# kitt_db01.net
KiCad netlist of a schematic drawn in EAGLE
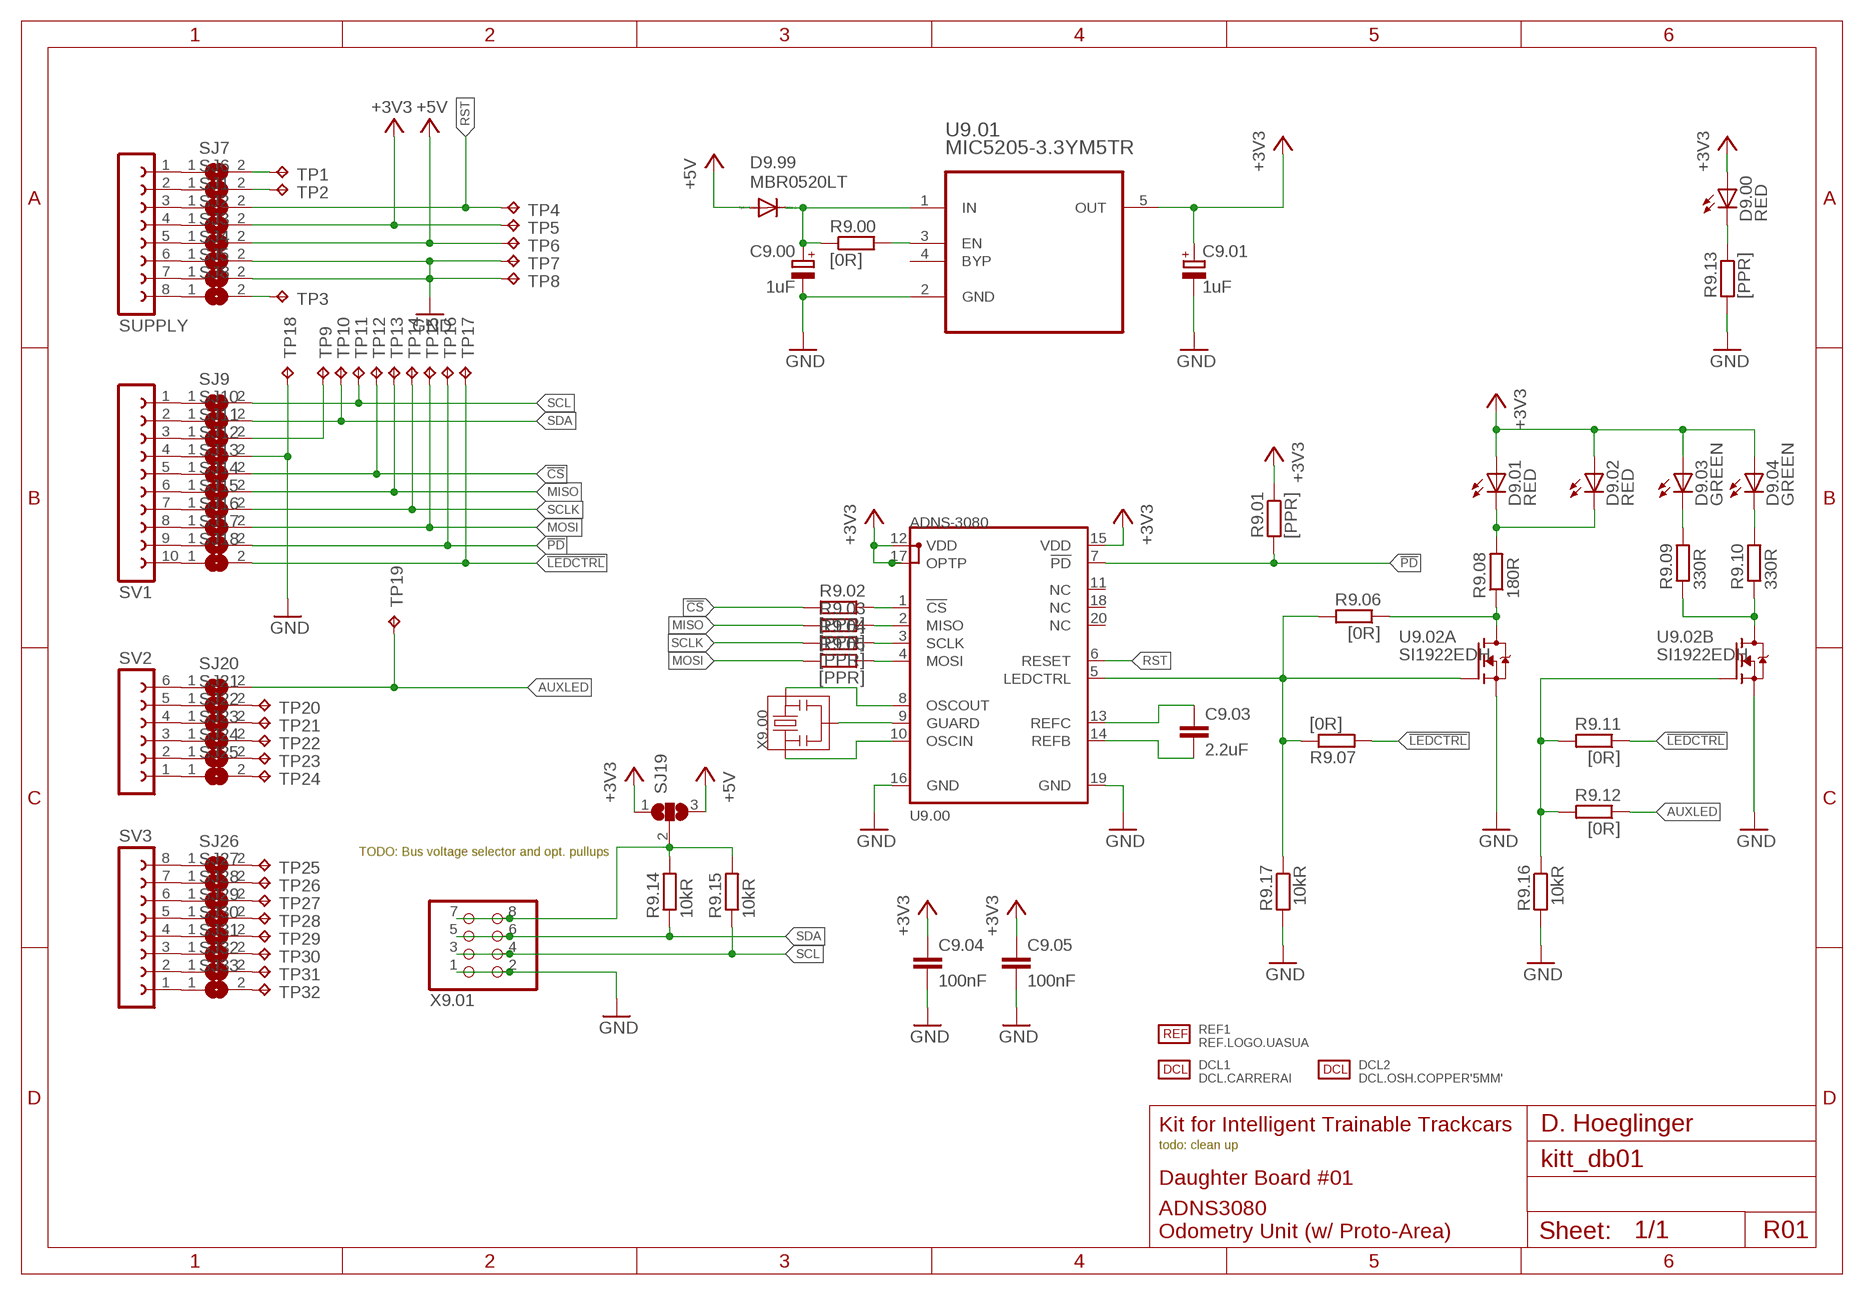
[diagram p0: schematic, sheet 1]

(export (version "E")
  (design (tool "Eeschema 10.0.6"))
  (components
    (comp (ref "C9.00")
      (value "1uF")
      (footprint "eagle-import:A_3216-18W")
      (libsource (lib "eagle-import") (part "CPOL-EUA/3216-18W"))
    )
    (comp (ref "C9.01")
      (value "1uF")
      (footprint "eagle-import:A_3216-18W")
      (libsource (lib "eagle-import") (part "CPOL-EUA/3216-18W"))
    )
    (comp (ref "C9.03")
      (value "2.2uF")
      (footprint "eagle-import:C1608")
      (libsource (lib "eagle-import") (part "C-EUC1608"))
    )
    (comp (ref "C9.04")
      (value "100nF")
      (footprint "eagle-import:C0805K")
      (libsource (lib "eagle-import") (part "C-EUC0805K"))
    )
    (comp (ref "C9.05")
      (value "100nF")
      (footprint "eagle-import:C0805K")
      (libsource (lib "eagle-import") (part "C-EUC0805K"))
    )
    (comp (ref "D9.00")
      (value "RED")
      (footprint "eagle-import:CHIP-LED0805")
      (libsource (lib "eagle-import") (part "LEDCHIP-LED0805"))
    )
    (comp (ref "D9.01")
      (value "RED")
      (footprint "eagle-import:LED5MM")
      (libsource (lib "eagle-import") (part "LED5MM"))
    )
    (comp (ref "D9.02")
      (value "RED")
      (footprint "eagle-import:CHIP-LED0805")
      (libsource (lib "eagle-import") (part "LEDCHIP-LED0805"))
    )
    (comp (ref "D9.03")
      (value "GREEN")
      (footprint "eagle-import:CHIP-LED0805")
      (libsource (lib "eagle-import") (part "LEDCHIP-LED0805"))
    )
    (comp (ref "D9.04")
      (value "GREEN")
      (footprint "eagle-import:CHIP-LED0805")
      (libsource (lib "eagle-import") (part "LEDCHIP-LED0805"))
    )
    (comp (ref "D9.99")
      (value "MBR0520LT")
      (footprint "eagle-import:SOD123")
      (libsource (lib "eagle-import") (part "MBR0520LT"))
    )
    (comp (ref "DCL1")
      (value "DCL.CARRERAI")
      (footprint "eagle-import:DCL.LOGO-CARRERAI.W30MM")
      (libsource (lib "eagle-import") (part "DCL.CARRERAI"))
    )
    (comp (ref "DCL2")
      (value "DCL.OSH.COPPER'5MM'")
      (footprint "eagle-import:DCL.LOGO-OSH.5MM")
      (libsource (lib "eagle-import") (part "DCL.OSH.COPPER'5MM'"))
    )
    (comp (ref "R9.00")
      (value "[0R]")
      (footprint "eagle-import:R0805")
      (libsource (lib "eagle-import") (part "R-EU_R0805"))
    )
    (comp (ref "R9.01")
      (value "[PPR]")
      (footprint "eagle-import:R0805")
      (libsource (lib "eagle-import") (part "R-EU_R0805"))
    )
    (comp (ref "R9.02")
      (value "[PPR]")
      (footprint "eagle-import:R0805")
      (libsource (lib "eagle-import") (part "R-EU_R0805"))
    )
    (comp (ref "R9.03")
      (value "[PPR]")
      (footprint "eagle-import:R0805")
      (libsource (lib "eagle-import") (part "R-EU_R0805"))
    )
    (comp (ref "R9.04")
      (value "[PPR]")
      (footprint "eagle-import:R0805")
      (libsource (lib "eagle-import") (part "R-EU_R0805"))
    )
    (comp (ref "R9.05")
      (value "[PPR]")
      (footprint "eagle-import:R0805")
      (libsource (lib "eagle-import") (part "R-EU_R0805"))
    )
    (comp (ref "R9.06")
      (value "[0R]")
      (footprint "eagle-import:R0805")
      (libsource (lib "eagle-import") (part "R-EU_R0805"))
    )
    (comp (ref "R9.07")
      (value "[0R]")
      (footprint "eagle-import:R0805")
      (libsource (lib "eagle-import") (part "R-EU_R0805"))
    )
    (comp (ref "R9.08")
      (value "180R")
      (footprint "eagle-import:R0805")
      (libsource (lib "eagle-import") (part "R-EU_R0805"))
    )
    (comp (ref "R9.09")
      (value "330R")
      (footprint "eagle-import:R0805")
      (libsource (lib "eagle-import") (part "R-EU_R0805"))
    )
    (comp (ref "R9.10")
      (value "330R")
      (footprint "eagle-import:R0805")
      (libsource (lib "eagle-import") (part "R-EU_R0805"))
    )
    (comp (ref "R9.11")
      (value "[0R]")
      (footprint "eagle-import:R0805")
      (libsource (lib "eagle-import") (part "R-EU_R0805"))
    )
    (comp (ref "R9.12")
      (value "[0R]")
      (footprint "eagle-import:R0805")
      (libsource (lib "eagle-import") (part "R-EU_R0805"))
    )
    (comp (ref "R9.13")
      (value "[PPR]")
      (footprint "eagle-import:R0805")
      (libsource (lib "eagle-import") (part "R-EU_R0805"))
    )
    (comp (ref "R9.14")
      (value "10kR")
      (footprint "eagle-import:R0805")
      (libsource (lib "eagle-import") (part "R-EU_R0805"))
    )
    (comp (ref "R9.15")
      (value "10kR")
      (footprint "eagle-import:R0805")
      (libsource (lib "eagle-import") (part "R-EU_R0805"))
    )
    (comp (ref "R9.16")
      (value "10kR")
      (footprint "eagle-import:R0805")
      (libsource (lib "eagle-import") (part "R-EU_R0805"))
    )
    (comp (ref "R9.17")
      (value "10kR")
      (footprint "eagle-import:R0805")
      (libsource (lib "eagle-import") (part "R-EU_R0805"))
    )
    (comp (ref "REF1")
      (value "REF.LOGO.UASUA")
      (footprint "eagle-import:REF_LOGO_UASUA")
      (libsource (lib "eagle-import") (part "REF.LOGO.UASUA"))
    )
    (comp (ref "SJ1") (value "SJ") (footprint "eagle-import:SJ") (libsource (lib "eagle-import") (part "SJ")))
    (comp (ref "SJ2") (value "SJ") (footprint "eagle-import:SJ") (libsource (lib "eagle-import") (part "SJ")))
    (comp (ref "SJ3") (value "SJ") (footprint "eagle-import:SJ") (libsource (lib "eagle-import") (part "SJ")))
    (comp (ref "SJ4") (value "SJ") (footprint "eagle-import:SJ") (libsource (lib "eagle-import") (part "SJ")))
    (comp (ref "SJ5") (value "SJ") (footprint "eagle-import:SJ") (libsource (lib "eagle-import") (part "SJ")))
    (comp (ref "SJ6") (value "SJ") (footprint "eagle-import:SJ") (libsource (lib "eagle-import") (part "SJ")))
    (comp (ref "SJ7") (value "SJ") (footprint "eagle-import:SJ") (libsource (lib "eagle-import") (part "SJ")))
    (comp (ref "SJ8") (value "SJ") (footprint "eagle-import:SJ") (libsource (lib "eagle-import") (part "SJ")))
    (comp (ref "SJ9") (value "SJ") (footprint "eagle-import:SJ") (libsource (lib "eagle-import") (part "SJ")))
    (comp (ref "SJ10")
      (value "SJ")
      (footprint "eagle-import:SJ")
      (libsource (lib "eagle-import") (part "SJ"))
    )
    (comp (ref "SJ11")
      (value "SJ")
      (footprint "eagle-import:SJ")
      (libsource (lib "eagle-import") (part "SJ"))
    )
    (comp (ref "SJ12")
      (value "SJ")
      (footprint "eagle-import:SJ")
      (libsource (lib "eagle-import") (part "SJ"))
    )
    (comp (ref "SJ13")
      (value "SJ")
      (footprint "eagle-import:SJ")
      (libsource (lib "eagle-import") (part "SJ"))
    )
    (comp (ref "SJ14")
      (value "SJ")
      (footprint "eagle-import:SJ")
      (libsource (lib "eagle-import") (part "SJ"))
    )
    (comp (ref "SJ15")
      (value "SJ")
      (footprint "eagle-import:SJ")
      (libsource (lib "eagle-import") (part "SJ"))
    )
    (comp (ref "SJ16")
      (value "SJ")
      (footprint "eagle-import:SJ")
      (libsource (lib "eagle-import") (part "SJ"))
    )
    (comp (ref "SJ17")
      (value "SJ")
      (footprint "eagle-import:SJ")
      (libsource (lib "eagle-import") (part "SJ"))
    )
    (comp (ref "SJ18")
      (value "SJ")
      (footprint "eagle-import:SJ")
      (libsource (lib "eagle-import") (part "SJ"))
    )
    (comp (ref "SJ19")
      (value "SJ2W")
      (footprint "eagle-import:SJ_2")
      (libsource (lib "eagle-import") (part "SJ2W"))
    )
    (comp (ref "SJ20")
      (value "SJ")
      (footprint "eagle-import:SJ")
      (libsource (lib "eagle-import") (part "SJ"))
    )
    (comp (ref "SJ21")
      (value "SJ")
      (footprint "eagle-import:SJ")
      (libsource (lib "eagle-import") (part "SJ"))
    )
    (comp (ref "SJ22")
      (value "SJ")
      (footprint "eagle-import:SJ")
      (libsource (lib "eagle-import") (part "SJ"))
    )
    (comp (ref "SJ23")
      (value "SJ")
      (footprint "eagle-import:SJ")
      (libsource (lib "eagle-import") (part "SJ"))
    )
    (comp (ref "SJ24")
      (value "SJ")
      (footprint "eagle-import:SJ")
      (libsource (lib "eagle-import") (part "SJ"))
    )
    (comp (ref "SJ25")
      (value "SJ")
      (footprint "eagle-import:SJ")
      (libsource (lib "eagle-import") (part "SJ"))
    )
    (comp (ref "SJ26")
      (value "SJ")
      (footprint "eagle-import:SJ")
      (libsource (lib "eagle-import") (part "SJ"))
    )
    (comp (ref "SJ27")
      (value "SJ")
      (footprint "eagle-import:SJ")
      (libsource (lib "eagle-import") (part "SJ"))
    )
    (comp (ref "SJ28")
      (value "SJ")
      (footprint "eagle-import:SJ")
      (libsource (lib "eagle-import") (part "SJ"))
    )
    (comp (ref "SJ29")
      (value "SJ")
      (footprint "eagle-import:SJ")
      (libsource (lib "eagle-import") (part "SJ"))
    )
    (comp (ref "SJ30")
      (value "SJ")
      (footprint "eagle-import:SJ")
      (libsource (lib "eagle-import") (part "SJ"))
    )
    (comp (ref "SJ31")
      (value "SJ")
      (footprint "eagle-import:SJ")
      (libsource (lib "eagle-import") (part "SJ"))
    )
    (comp (ref "SJ32")
      (value "SJ")
      (footprint "eagle-import:SJ")
      (libsource (lib "eagle-import") (part "SJ"))
    )
    (comp (ref "SJ33")
      (value "SJ")
      (footprint "eagle-import:SJ")
      (libsource (lib "eagle-import") (part "SJ"))
    )
    (comp (ref "SUPPLY")
      (value "FE08-1")
      (footprint "eagle-import:FE08")
      (libsource (lib "eagle-import") (part "FE08-1"))
    )
    (comp (ref "SV1")
      (value "FE10-1")
      (footprint "eagle-import:FE10")
      (libsource (lib "eagle-import") (part "FE10-1"))
    )
    (comp (ref "SV2")
      (value "FE06-1")
      (footprint "eagle-import:FE06")
      (libsource (lib "eagle-import") (part "FE06-1"))
    )
    (comp (ref "SV3")
      (value "FE08-1")
      (footprint "eagle-import:FE08")
      (libsource (lib "eagle-import") (part "FE08-1"))
    )
    (comp (ref "TP1")
      (value "TPPAD1-13")
      (footprint "eagle-import:P1-13")
      (libsource (lib "eagle-import") (part "TPPAD1-13"))
    )
    (comp (ref "TP2")
      (value "TPPAD1-13")
      (footprint "eagle-import:P1-13")
      (libsource (lib "eagle-import") (part "TPPAD1-13"))
    )
    (comp (ref "TP3")
      (value "TPPAD1-13")
      (footprint "eagle-import:P1-13")
      (libsource (lib "eagle-import") (part "TPPAD1-13"))
    )
    (comp (ref "TP4")
      (value "TPPAD1-13")
      (footprint "eagle-import:P1-13")
      (libsource (lib "eagle-import") (part "TPPAD1-13"))
    )
    (comp (ref "TP5")
      (value "TPPAD1-13")
      (footprint "eagle-import:P1-13")
      (libsource (lib "eagle-import") (part "TPPAD1-13"))
    )
    (comp (ref "TP6")
      (value "TPPAD1-13")
      (footprint "eagle-import:P1-13")
      (libsource (lib "eagle-import") (part "TPPAD1-13"))
    )
    (comp (ref "TP7")
      (value "TPPAD1-13")
      (footprint "eagle-import:P1-13")
      (libsource (lib "eagle-import") (part "TPPAD1-13"))
    )
    (comp (ref "TP8")
      (value "TPPAD1-13")
      (footprint "eagle-import:P1-13")
      (libsource (lib "eagle-import") (part "TPPAD1-13"))
    )
    (comp (ref "TP9")
      (value "TPPAD1-13")
      (footprint "eagle-import:P1-13")
      (libsource (lib "eagle-import") (part "TPPAD1-13"))
    )
    (comp (ref "TP10")
      (value "TPPAD1-13")
      (footprint "eagle-import:P1-13")
      (libsource (lib "eagle-import") (part "TPPAD1-13"))
    )
    (comp (ref "TP11")
      (value "TPPAD1-13")
      (footprint "eagle-import:P1-13")
      (libsource (lib "eagle-import") (part "TPPAD1-13"))
    )
    (comp (ref "TP12")
      (value "TPPAD1-13")
      (footprint "eagle-import:P1-13")
      (libsource (lib "eagle-import") (part "TPPAD1-13"))
    )
    (comp (ref "TP13")
      (value "TPPAD1-13")
      (footprint "eagle-import:P1-13")
      (libsource (lib "eagle-import") (part "TPPAD1-13"))
    )
    (comp (ref "TP14")
      (value "TPPAD1-13")
      (footprint "eagle-import:P1-13")
      (libsource (lib "eagle-import") (part "TPPAD1-13"))
    )
    (comp (ref "TP15")
      (value "TPPAD1-13")
      (footprint "eagle-import:P1-13")
      (libsource (lib "eagle-import") (part "TPPAD1-13"))
    )
    (comp (ref "TP16")
      (value "TPPAD1-13")
      (footprint "eagle-import:P1-13")
      (libsource (lib "eagle-import") (part "TPPAD1-13"))
    )
    (comp (ref "TP17")
      (value "TPPAD1-13")
      (footprint "eagle-import:P1-13")
      (libsource (lib "eagle-import") (part "TPPAD1-13"))
    )
    (comp (ref "TP18")
      (value "TPPAD1-13")
      (footprint "eagle-import:P1-13")
      (libsource (lib "eagle-import") (part "TPPAD1-13"))
    )
    (comp (ref "TP19")
      (value "TPPAD1-13")
      (footprint "eagle-import:P1-13")
      (libsource (lib "eagle-import") (part "TPPAD1-13"))
    )
    (comp (ref "TP20")
      (value "TPPAD1-13")
      (footprint "eagle-import:P1-13")
      (libsource (lib "eagle-import") (part "TPPAD1-13"))
    )
    (comp (ref "TP21")
      (value "TPPAD1-13")
      (footprint "eagle-import:P1-13")
      (libsource (lib "eagle-import") (part "TPPAD1-13"))
    )
    (comp (ref "TP22")
      (value "TPPAD1-13")
      (footprint "eagle-import:P1-13")
      (libsource (lib "eagle-import") (part "TPPAD1-13"))
    )
    (comp (ref "TP23")
      (value "TPPAD1-13")
      (footprint "eagle-import:P1-13")
      (libsource (lib "eagle-import") (part "TPPAD1-13"))
    )
    (comp (ref "TP24")
      (value "TPPAD1-13")
      (footprint "eagle-import:P1-13")
      (libsource (lib "eagle-import") (part "TPPAD1-13"))
    )
    (comp (ref "TP25")
      (value "TPPAD1-13")
      (footprint "eagle-import:P1-13")
      (libsource (lib "eagle-import") (part "TPPAD1-13"))
    )
    (comp (ref "TP26")
      (value "TPPAD1-13")
      (footprint "eagle-import:P1-13")
      (libsource (lib "eagle-import") (part "TPPAD1-13"))
    )
    (comp (ref "TP27")
      (value "TPPAD1-13")
      (footprint "eagle-import:P1-13")
      (libsource (lib "eagle-import") (part "TPPAD1-13"))
    )
    (comp (ref "TP28")
      (value "TPPAD1-13")
      (footprint "eagle-import:P1-13")
      (libsource (lib "eagle-import") (part "TPPAD1-13"))
    )
    (comp (ref "TP29")
      (value "TPPAD1-13")
      (footprint "eagle-import:P1-13")
      (libsource (lib "eagle-import") (part "TPPAD1-13"))
    )
    (comp (ref "TP30")
      (value "TPPAD1-13")
      (footprint "eagle-import:P1-13")
      (libsource (lib "eagle-import") (part "TPPAD1-13"))
    )
    (comp (ref "TP31")
      (value "TPPAD1-13")
      (footprint "eagle-import:P1-13")
      (libsource (lib "eagle-import") (part "TPPAD1-13"))
    )
    (comp (ref "TP32")
      (value "TPPAD1-13")
      (footprint "eagle-import:P1-13")
      (libsource (lib "eagle-import") (part "TPPAD1-13"))
    )
    (comp (ref "U9.00")
      (value "ADNS-3080")
      (footprint "eagle-import:ADNS-3080")
      (libsource (lib "eagle-import") (part "ADNS-3080"))
    )
    (comp (ref "U9.01")
      (value "MIC5205-3.3YM5TR")
      (footprint "eagle-import:SOT95P280X130-5N")
      (fields (field (name "MF") "Microchip") (field (name "MP") "MIC5205-3.3YM5-TR"))
      (libsource (lib "eagle-import") (part "MIC5205-3.3YM5TR"))
    )
    (comp (ref "U9.02")
      (value "SI1922EDH")
      (footprint "eagle-import:SC70-6")
      (libsource (lib "eagle-import") (part "SI1922EDH"))
    )
    (comp (ref "X9.00")
      (value "RESON")
      (footprint "eagle-import:RESON-SMD")
      (libsource (lib "eagle-import") (part "RESON"))
    )
    (comp (ref "X9.01")
      (value "PINHD-2X4/90")
      (footprint "eagle-import:2X04_90")
      (libsource (lib "eagle-import") (part "PINHD-2X4/90"))
    )
  )
  (nets
    (net (code "1") (name "+3V3") (class "Default")
      (node (ref "C9.01") (pin "+") (pinfunction "+_+") (pintype "passive"))
      (node (ref "C9.04") (pin "1") (pinfunction "1_1") (pintype "passive"))
      (node (ref "C9.05") (pin "1") (pinfunction "1_1") (pintype "passive"))
      (node (ref "D9.00") (pin "A") (pinfunction "A_A") (pintype "passive"))
      (node (ref "D9.01") (pin "A") (pinfunction "A_A") (pintype "passive"))
      (node (ref "D9.02") (pin "A") (pinfunction "A_A") (pintype "passive"))
      (node (ref "D9.03") (pin "A") (pinfunction "A_A") (pintype "passive"))
      (node (ref "D9.04") (pin "A") (pinfunction "A_A") (pintype "passive"))
      (node (ref "R9.01") (pin "1") (pinfunction "1_1") (pintype "passive"))
      (node (ref "SJ19") (pin "1") (pinfunction "1_1") (pintype "passive"))
      (node (ref "SJ2") (pin "2") (pinfunction "2_2") (pintype "passive"))
      (node (ref "TP5") (pin "TP") (pinfunction "TP_TP") (pintype "input"))
      (node (ref "U9.00") (pin "12") (pinfunction "VDD_12") (pintype "power_in"))
      (node (ref "U9.00") (pin "15") (pinfunction "VDD_15") (pintype "power_in"))
      (node (ref "U9.00") (pin "17") (pinfunction "OPTP_17") (pintype "open_collector"))
      (node (ref "U9.01") (pin "5") (pinfunction "OUT_5") (pintype "output"))
    )
    (net (code "2") (name "+5V") (class "Default")
      (node (ref "D9.99") (pin "A") (pinfunction "A_A") (pintype "passive"))
      (node (ref "SJ19") (pin "3") (pinfunction "3_3") (pintype "passive"))
      (node (ref "SJ3") (pin "2") (pinfunction "2_2") (pintype "passive"))
      (node (ref "TP6") (pin "TP") (pinfunction "TP_TP") (pintype "input"))
    )
    (net (code "3") (name "/~{CS}") (class "Default")
      (node (ref "R9.02") (pin "2") (pinfunction "2_2") (pintype "passive"))
      (node (ref "SJ13") (pin "2") (pinfunction "2_2") (pintype "passive"))
      (node (ref "TP12") (pin "TP") (pinfunction "TP_TP") (pintype "input"))
    )
    (net (code "4") (name "/~{LEDCTRL}") (class "Default")
      (node (ref "R9.07") (pin "2") (pinfunction "2_2") (pintype "passive"))
      (node (ref "R9.11") (pin "1") (pinfunction "1_1") (pintype "passive"))
      (node (ref "SJ18") (pin "2") (pinfunction "2_2") (pintype "passive"))
      (node (ref "TP17") (pin "TP") (pinfunction "TP_TP") (pintype "input"))
    )
    (net (code "5") (name "/~{PD}") (class "Default")
      (node (ref "R9.01") (pin "2") (pinfunction "2_2") (pintype "passive"))
      (node (ref "SJ17") (pin "2") (pinfunction "2_2") (pintype "passive"))
      (node (ref "TP16") (pin "TP") (pinfunction "TP_TP") (pintype "input"))
      (node (ref "U9.00") (pin "7") (pinfunction "~{PD}_7") (pintype "input"))
    )
    (net (code "6") (name "AUXLED") (class "Default")
      (node (ref "R9.12") (pin "1") (pinfunction "1_1") (pintype "passive"))
      (node (ref "SJ20") (pin "2") (pinfunction "2_2") (pintype "passive"))
      (node (ref "TP19") (pin "TP") (pinfunction "TP_TP") (pintype "input"))
    )
    (net (code "7") (name "GND") (class "Default")
      (node (ref "C9.00") (pin "-") (pinfunction "-_-") (pintype "passive"))
      (node (ref "C9.01") (pin "-") (pinfunction "-_-") (pintype "passive"))
      (node (ref "C9.04") (pin "2") (pinfunction "2_2") (pintype "passive"))
      (node (ref "C9.05") (pin "2") (pinfunction "2_2") (pintype "passive"))
      (node (ref "R9.13") (pin "2") (pinfunction "2_2") (pintype "passive"))
      (node (ref "R9.16") (pin "2") (pinfunction "2_2") (pintype "passive"))
      (node (ref "R9.17") (pin "2") (pinfunction "2_2") (pintype "passive"))
      (node (ref "SJ12") (pin "2") (pinfunction "2_2") (pintype "passive"))
      (node (ref "SJ4") (pin "2") (pinfunction "2_2") (pintype "passive"))
      (node (ref "SJ5") (pin "2") (pinfunction "2_2") (pintype "passive"))
      (node (ref "TP18") (pin "TP") (pinfunction "TP_TP") (pintype "input"))
      (node (ref "TP7") (pin "TP") (pinfunction "TP_TP") (pintype "input"))
      (node (ref "TP8") (pin "TP") (pinfunction "TP_TP") (pintype "input"))
      (node (ref "U9.00") (pin "16") (pinfunction "GND_16") (pintype "power_in"))
      (node (ref "U9.00") (pin "19") (pinfunction "GND_19") (pintype "power_in"))
      (node (ref "U9.01") (pin "2") (pinfunction "GND_2") (pintype "passive"))
      (node (ref "U9.02") (pin "1") (pinfunction "S_1") (pintype "passive"))
      (node (ref "U9.02") (pin "4") (pinfunction "S_4") (pintype "passive"))
      (node (ref "X9.01") (pin "1") (pinfunction "1_1") (pintype "passive"))
      (node (ref "X9.01") (pin "2") (pinfunction "2_2") (pintype "passive"))
    )
    (net (code "8") (name "MISO") (class "Default")
      (node (ref "R9.03") (pin "2") (pinfunction "2_2") (pintype "passive"))
      (node (ref "SJ14") (pin "2") (pinfunction "2_2") (pintype "passive"))
      (node (ref "TP13") (pin "TP") (pinfunction "TP_TP") (pintype "input"))
    )
    (net (code "9") (name "MOSI") (class "Default")
      (node (ref "R9.05") (pin "2") (pinfunction "2_2") (pintype "passive"))
      (node (ref "SJ16") (pin "2") (pinfunction "2_2") (pintype "passive"))
      (node (ref "TP15") (pin "TP") (pinfunction "TP_TP") (pintype "input"))
    )
    (net (code "10") (name "Net-(D9.00-PadC)") (class "Default")
      (node (ref "D9.00") (pin "C") (pinfunction "C_C") (pintype "passive"))
      (node (ref "R9.13") (pin "1") (pinfunction "1_1") (pintype "passive"))
    )
    (net (code "11") (name "Net-(D9.01-C)") (class "Default")
      (node (ref "D9.01") (pin "K") (pinfunction "C_K") (pintype "passive"))
      (node (ref "D9.02") (pin "C") (pinfunction "C_C") (pintype "passive"))
      (node (ref "R9.08") (pin "2") (pinfunction "2_2") (pintype "passive"))
    )
    (net (code "12") (name "Net-(D9.03-PadC)") (class "Default")
      (node (ref "D9.03") (pin "C") (pinfunction "C_C") (pintype "passive"))
      (node (ref "R9.09") (pin "2") (pinfunction "2_2") (pintype "passive"))
    )
    (net (code "13") (name "Net-(D9.04-PadC)") (class "Default")
      (node (ref "D9.04") (pin "C") (pinfunction "C_C") (pintype "passive"))
      (node (ref "R9.10") (pin "2") (pinfunction "2_2") (pintype "passive"))
    )
    (net (code "14") (name "Net-(R9.14-Pad2)") (class "Default")
      (node (ref "R9.14") (pin "2") (pinfunction "2_2") (pintype "passive"))
      (node (ref "R9.15") (pin "2") (pinfunction "2_2") (pintype "passive"))
      (node (ref "SJ19") (pin "2") (pinfunction "2_2") (pintype "passive"))
      (node (ref "X9.01") (pin "7") (pinfunction "7_7") (pintype "passive"))
      (node (ref "X9.01") (pin "8") (pinfunction "8_8") (pintype "passive"))
    )
    (net (code "15") (name "Net-(SJ1-Pad1)") (class "Default")
      (node (ref "SJ1") (pin "1") (pinfunction "1_1") (pintype "passive"))
      (node (ref "SUPPLY") (pin "3") (pinfunction "3_3") (pintype "passive"))
    )
    (net (code "16") (name "Net-(SJ2-Pad1)") (class "Default")
      (node (ref "SJ2") (pin "1") (pinfunction "1_1") (pintype "passive"))
      (node (ref "SUPPLY") (pin "4") (pinfunction "4_4") (pintype "passive"))
    )
    (net (code "17") (name "Net-(SJ3-Pad1)") (class "Default")
      (node (ref "SJ3") (pin "1") (pinfunction "1_1") (pintype "passive"))
      (node (ref "SUPPLY") (pin "5") (pinfunction "5_5") (pintype "passive"))
    )
    (net (code "18") (name "Net-(SJ4-Pad1)") (class "Default")
      (node (ref "SJ4") (pin "1") (pinfunction "1_1") (pintype "passive"))
      (node (ref "SUPPLY") (pin "6") (pinfunction "6_6") (pintype "passive"))
    )
    (net (code "19") (name "Net-(SJ5-Pad1)") (class "Default")
      (node (ref "SJ5") (pin "1") (pinfunction "1_1") (pintype "passive"))
      (node (ref "SUPPLY") (pin "7") (pinfunction "7_7") (pintype "passive"))
    )
    (net (code "20") (name "Net-(SJ6-Pad1)") (class "Default")
      (node (ref "SJ6") (pin "1") (pinfunction "1_1") (pintype "passive"))
      (node (ref "SUPPLY") (pin "2") (pinfunction "2_2") (pintype "passive"))
    )
    (net (code "21") (name "Net-(SJ6-Pad2)") (class "Default")
      (node (ref "SJ6") (pin "2") (pinfunction "2_2") (pintype "passive"))
      (node (ref "TP2") (pin "TP") (pinfunction "TP_TP") (pintype "input"))
    )
    (net (code "22") (name "Net-(SJ7-Pad1)") (class "Default")
      (node (ref "SJ7") (pin "1") (pinfunction "1_1") (pintype "passive"))
      (node (ref "SUPPLY") (pin "1") (pinfunction "1_1") (pintype "passive"))
    )
    (net (code "23") (name "Net-(SJ7-Pad2)") (class "Default")
      (node (ref "SJ7") (pin "2") (pinfunction "2_2") (pintype "passive"))
      (node (ref "TP1") (pin "TP") (pinfunction "TP_TP") (pintype "input"))
    )
    (net (code "24") (name "Net-(SJ8-Pad1)") (class "Default")
      (node (ref "SJ8") (pin "1") (pinfunction "1_1") (pintype "passive"))
      (node (ref "SUPPLY") (pin "8") (pinfunction "8_8") (pintype "passive"))
    )
    (net (code "25") (name "Net-(SJ8-Pad2)") (class "Default")
      (node (ref "SJ8") (pin "2") (pinfunction "2_2") (pintype "passive"))
      (node (ref "TP3") (pin "TP") (pinfunction "TP_TP") (pintype "input"))
    )
    (net (code "26") (name "Net-(SJ9-Pad1)") (class "Default")
      (node (ref "SJ9") (pin "1") (pinfunction "1_1") (pintype "passive"))
      (node (ref "SV1") (pin "1") (pinfunction "1_1") (pintype "passive"))
    )
    (net (code "27") (name "Net-(SJ10-Pad1)") (class "Default")
      (node (ref "SJ10") (pin "1") (pinfunction "1_1") (pintype "passive"))
      (node (ref "SV1") (pin "2") (pinfunction "2_2") (pintype "passive"))
    )
    (net (code "28") (name "Net-(SJ11-Pad1)") (class "Default")
      (node (ref "SJ11") (pin "1") (pinfunction "1_1") (pintype "passive"))
      (node (ref "SV1") (pin "3") (pinfunction "3_3") (pintype "passive"))
    )
    (net (code "29") (name "Net-(SJ11-Pad2)") (class "Default")
      (node (ref "SJ11") (pin "2") (pinfunction "2_2") (pintype "passive"))
      (node (ref "TP9") (pin "TP") (pinfunction "TP_TP") (pintype "input"))
    )
    (net (code "30") (name "Net-(SJ12-Pad1)") (class "Default")
      (node (ref "SJ12") (pin "1") (pinfunction "1_1") (pintype "passive"))
      (node (ref "SV1") (pin "4") (pinfunction "4_4") (pintype "passive"))
    )
    (net (code "31") (name "Net-(SJ13-Pad1)") (class "Default")
      (node (ref "SJ13") (pin "1") (pinfunction "1_1") (pintype "passive"))
      (node (ref "SV1") (pin "5") (pinfunction "5_5") (pintype "passive"))
    )
    (net (code "32") (name "Net-(SJ14-Pad1)") (class "Default")
      (node (ref "SJ14") (pin "1") (pinfunction "1_1") (pintype "passive"))
      (node (ref "SV1") (pin "6") (pinfunction "6_6") (pintype "passive"))
    )
    (net (code "33") (name "Net-(SJ15-Pad1)") (class "Default")
      (node (ref "SJ15") (pin "1") (pinfunction "1_1") (pintype "passive"))
      (node (ref "SV1") (pin "7") (pinfunction "7_7") (pintype "passive"))
    )
    (net (code "34") (name "Net-(SJ16-Pad1)") (class "Default")
      (node (ref "SJ16") (pin "1") (pinfunction "1_1") (pintype "passive"))
      (node (ref "SV1") (pin "8") (pinfunction "8_8") (pintype "passive"))
    )
    (net (code "35") (name "Net-(SJ17-Pad1)") (class "Default")
      (node (ref "SJ17") (pin "1") (pinfunction "1_1") (pintype "passive"))
      (node (ref "SV1") (pin "9") (pinfunction "9_9") (pintype "passive"))
    )
    (net (code "36") (name "Net-(SJ18-Pad1)") (class "Default")
      (node (ref "SJ18") (pin "1") (pinfunction "1_1") (pintype "passive"))
      (node (ref "SV1") (pin "10") (pinfunction "10_10") (pintype "passive"))
    )
    (net (code "37") (name "Net-(SJ20-Pad1)") (class "Default")
      (node (ref "SJ20") (pin "1") (pinfunction "1_1") (pintype "passive"))
      (node (ref "SV2") (pin "6") (pinfunction "6_6") (pintype "passive"))
    )
    (net (code "38") (name "Net-(SJ21-Pad1)") (class "Default")
      (node (ref "SJ21") (pin "1") (pinfunction "1_1") (pintype "passive"))
      (node (ref "SV2") (pin "5") (pinfunction "5_5") (pintype "passive"))
    )
    (net (code "39") (name "Net-(SJ21-Pad2)") (class "Default")
      (node (ref "SJ21") (pin "2") (pinfunction "2_2") (pintype "passive"))
      (node (ref "TP20") (pin "TP") (pinfunction "TP_TP") (pintype "input"))
    )
    (net (code "40") (name "Net-(SJ22-Pad1)") (class "Default")
      (node (ref "SJ22") (pin "1") (pinfunction "1_1") (pintype "passive"))
      (node (ref "SV2") (pin "4") (pinfunction "4_4") (pintype "passive"))
    )
    (net (code "41") (name "Net-(SJ22-Pad2)") (class "Default")
      (node (ref "SJ22") (pin "2") (pinfunction "2_2") (pintype "passive"))
      (node (ref "TP21") (pin "TP") (pinfunction "TP_TP") (pintype "input"))
    )
    (net (code "42") (name "Net-(SJ23-Pad1)") (class "Default")
      (node (ref "SJ23") (pin "1") (pinfunction "1_1") (pintype "passive"))
      (node (ref "SV2") (pin "3") (pinfunction "3_3") (pintype "passive"))
    )
    (net (code "43") (name "Net-(SJ23-Pad2)") (class "Default")
      (node (ref "SJ23") (pin "2") (pinfunction "2_2") (pintype "passive"))
      (node (ref "TP22") (pin "TP") (pinfunction "TP_TP") (pintype "input"))
    )
    (net (code "44") (name "Net-(SJ24-Pad1)") (class "Default")
      (node (ref "SJ24") (pin "1") (pinfunction "1_1") (pintype "passive"))
      (node (ref "SV2") (pin "2") (pinfunction "2_2") (pintype "passive"))
    )
    (net (code "45") (name "Net-(SJ24-Pad2)") (class "Default")
      (node (ref "SJ24") (pin "2") (pinfunction "2_2") (pintype "passive"))
      (node (ref "TP23") (pin "TP") (pinfunction "TP_TP") (pintype "input"))
    )
    (net (code "46") (name "Net-(SJ25-Pad1)") (class "Default")
      (node (ref "SJ25") (pin "1") (pinfunction "1_1") (pintype "passive"))
      (node (ref "SV2") (pin "1") (pinfunction "1_1") (pintype "passive"))
    )
    (net (code "47") (name "Net-(SJ25-Pad2)") (class "Default")
      (node (ref "SJ25") (pin "2") (pinfunction "2_2") (pintype "passive"))
      (node (ref "TP24") (pin "TP") (pinfunction "TP_TP") (pintype "input"))
    )
    (net (code "48") (name "Net-(SJ26-Pad1)") (class "Default")
      (node (ref "SJ26") (pin "1") (pinfunction "1_1") (pintype "passive"))
      (node (ref "SV3") (pin "8") (pinfunction "8_8") (pintype "passive"))
    )
    (net (code "49") (name "Net-(SJ26-Pad2)") (class "Default")
      (node (ref "SJ26") (pin "2") (pinfunction "2_2") (pintype "passive"))
      (node (ref "TP25") (pin "TP") (pinfunction "TP_TP") (pintype "input"))
    )
    (net (code "50") (name "Net-(SJ27-Pad1)") (class "Default")
      (node (ref "SJ27") (pin "1") (pinfunction "1_1") (pintype "passive"))
      (node (ref "SV3") (pin "7") (pinfunction "7_7") (pintype "passive"))
    )
    (net (code "51") (name "Net-(SJ27-Pad2)") (class "Default")
      (node (ref "SJ27") (pin "2") (pinfunction "2_2") (pintype "passive"))
      (node (ref "TP26") (pin "TP") (pinfunction "TP_TP") (pintype "input"))
    )
    (net (code "52") (name "Net-(SJ28-Pad1)") (class "Default")
      (node (ref "SJ28") (pin "1") (pinfunction "1_1") (pintype "passive"))
      (node (ref "SV3") (pin "6") (pinfunction "6_6") (pintype "passive"))
    )
    (net (code "53") (name "Net-(SJ28-Pad2)") (class "Default")
      (node (ref "SJ28") (pin "2") (pinfunction "2_2") (pintype "passive"))
      (node (ref "TP27") (pin "TP") (pinfunction "TP_TP") (pintype "input"))
    )
    (net (code "54") (name "Net-(SJ29-Pad1)") (class "Default")
      (node (ref "SJ29") (pin "1") (pinfunction "1_1") (pintype "passive"))
      (node (ref "SV3") (pin "5") (pinfunction "5_5") (pintype "passive"))
    )
    (net (code "55") (name "Net-(SJ29-Pad2)") (class "Default")
      (node (ref "SJ29") (pin "2") (pinfunction "2_2") (pintype "passive"))
      (node (ref "TP28") (pin "TP") (pinfunction "TP_TP") (pintype "input"))
    )
    (net (code "56") (name "Net-(SJ30-Pad1)") (class "Default")
      (node (ref "SJ30") (pin "1") (pinfunction "1_1") (pintype "passive"))
      (node (ref "SV3") (pin "4") (pinfunction "4_4") (pintype "passive"))
    )
    (net (code "57") (name "Net-(SJ30-Pad2)") (class "Default")
      (node (ref "SJ30") (pin "2") (pinfunction "2_2") (pintype "passive"))
      (node (ref "TP29") (pin "TP") (pinfunction "TP_TP") (pintype "input"))
    )
    (net (code "58") (name "Net-(SJ31-Pad1)") (class "Default")
      (node (ref "SJ31") (pin "1") (pinfunction "1_1") (pintype "passive"))
      (node (ref "SV3") (pin "3") (pinfunction "3_3") (pintype "passive"))
    )
    (net (code "59") (name "Net-(SJ31-Pad2)") (class "Default")
      (node (ref "SJ31") (pin "2") (pinfunction "2_2") (pintype "passive"))
      (node (ref "TP30") (pin "TP") (pinfunction "TP_TP") (pintype "input"))
    )
    (net (code "60") (name "Net-(SJ32-Pad1)") (class "Default")
      (node (ref "SJ32") (pin "1") (pinfunction "1_1") (pintype "passive"))
      (node (ref "SV3") (pin "2") (pinfunction "2_2") (pintype "passive"))
    )
    (net (code "61") (name "Net-(SJ32-Pad2)") (class "Default")
      (node (ref "SJ32") (pin "2") (pinfunction "2_2") (pintype "passive"))
      (node (ref "TP31") (pin "TP") (pinfunction "TP_TP") (pintype "input"))
    )
    (net (code "62") (name "Net-(SJ33-Pad1)") (class "Default")
      (node (ref "SJ33") (pin "1") (pinfunction "1_1") (pintype "passive"))
      (node (ref "SV3") (pin "1") (pinfunction "1_1") (pintype "passive"))
    )
    (net (code "63") (name "Net-(SJ33-Pad2)") (class "Default")
      (node (ref "SJ33") (pin "2") (pinfunction "2_2") (pintype "passive"))
      (node (ref "TP32") (pin "TP") (pinfunction "TP_TP") (pintype "input"))
    )
    (net (code "64") (name "Net-(U9.00-GUARD)") (class "Default")
      (node (ref "U9.00") (pin "9") (pinfunction "GUARD_9") (pintype "power_in"))
      (node (ref "X9.00") (pin "2") (pinfunction "2_2") (pintype "passive"))
    )
    (net (code "65") (name "Net-(U9.00-LEDCTRL)") (class "Default")
      (node (ref "R9.06") (pin "2") (pinfunction "2_2") (pintype "passive"))
      (node (ref "R9.07") (pin "1") (pinfunction "1_1") (pintype "passive"))
      (node (ref "R9.17") (pin "1") (pinfunction "1_1") (pintype "passive"))
      (node (ref "U9.00") (pin "5") (pinfunction "LEDCTRL_5") (pintype "output"))
      (node (ref "U9.02") (pin "2") (pinfunction "G_2") (pintype "passive"))
    )
    (net (code "66") (name "Net-(U9.00-MISO)") (class "Default")
      (node (ref "R9.03") (pin "1") (pinfunction "1_1") (pintype "passive"))
      (node (ref "U9.00") (pin "2") (pinfunction "MISO_2") (pintype "output"))
    )
    (net (code "67") (name "Net-(U9.00-MOSI)") (class "Default")
      (node (ref "R9.05") (pin "1") (pinfunction "1_1") (pintype "passive"))
      (node (ref "U9.00") (pin "4") (pinfunction "MOSI_4") (pintype "input"))
    )
    (net (code "68") (name "Net-(U9.00-OSCIN)") (class "Default")
      (node (ref "U9.00") (pin "10") (pinfunction "OSCIN_10") (pintype "input"))
      (node (ref "X9.00") (pin "1") (pinfunction "1_1") (pintype "passive"))
    )
    (net (code "69") (name "Net-(U9.00-OSCOUT)") (class "Default")
      (node (ref "U9.00") (pin "8") (pinfunction "OSCOUT_8") (pintype "output"))
      (node (ref "X9.00") (pin "3") (pinfunction "3_3") (pintype "passive"))
    )
    (net (code "70") (name "Net-(U9.00-REFB)") (class "Default")
      (node (ref "C9.03") (pin "2") (pinfunction "2_2") (pintype "passive"))
      (node (ref "U9.00") (pin "14") (pinfunction "REFB_14") (pintype "input"))
    )
    (net (code "71") (name "Net-(U9.00-REFC)") (class "Default")
      (node (ref "C9.03") (pin "1") (pinfunction "1_1") (pintype "passive"))
      (node (ref "U9.00") (pin "13") (pinfunction "REFC_13") (pintype "input"))
    )
    (net (code "72") (name "Net-(U9.00-SCLK)") (class "Default")
      (node (ref "R9.04") (pin "1") (pinfunction "1_1") (pintype "passive"))
      (node (ref "U9.00") (pin "3") (pinfunction "SCLK_3") (pintype "input"))
    )
    (net (code "73") (name "Net-(U9.00-~{CS})") (class "Default")
      (node (ref "R9.02") (pin "1") (pinfunction "1_1") (pintype "passive"))
      (node (ref "U9.00") (pin "1") (pinfunction "~{CS}_1") (pintype "input"))
    )
    (net (code "74") (name "Net-(U9.01-EN)") (class "Default")
      (node (ref "R9.00") (pin "2") (pinfunction "2_2") (pintype "passive"))
      (node (ref "U9.01") (pin "3") (pinfunction "EN_3") (pintype "input"))
    )
    (net (code "75") (name "Net-(U9.01-IN)") (class "Default")
      (node (ref "C9.00") (pin "+") (pinfunction "+_+") (pintype "passive"))
      (node (ref "D9.99") (pin "C") (pinfunction "C_C") (pintype "passive"))
      (node (ref "R9.00") (pin "1") (pinfunction "1_1") (pintype "passive"))
      (node (ref "U9.01") (pin "1") (pinfunction "IN_1") (pintype "input"))
    )
    (net (code "76") (name "Net-(U9.02A-D)") (class "Default")
      (node (ref "R9.06") (pin "1") (pinfunction "1_1") (pintype "passive"))
      (node (ref "R9.08") (pin "1") (pinfunction "1_1") (pintype "passive"))
      (node (ref "U9.02") (pin "6") (pinfunction "D_6") (pintype "passive"))
    )
    (net (code "77") (name "Net-(U9.02B-D)") (class "Default")
      (node (ref "R9.09") (pin "1") (pinfunction "1_1") (pintype "passive"))
      (node (ref "R9.10") (pin "1") (pinfunction "1_1") (pintype "passive"))
      (node (ref "U9.02") (pin "3") (pinfunction "D_3") (pintype "passive"))
    )
    (net (code "78") (name "Net-(U9.02B-G)") (class "Default")
      (node (ref "R9.11") (pin "2") (pinfunction "2_2") (pintype "passive"))
      (node (ref "R9.12") (pin "2") (pinfunction "2_2") (pintype "passive"))
      (node (ref "R9.16") (pin "1") (pinfunction "1_1") (pintype "passive"))
      (node (ref "U9.02") (pin "5") (pinfunction "G_5") (pintype "passive"))
    )
    (net (code "79") (name "RST") (class "Default")
      (node (ref "SJ1") (pin "2") (pinfunction "2_2") (pintype "passive"))
      (node (ref "TP4") (pin "TP") (pinfunction "TP_TP") (pintype "input"))
      (node (ref "U9.00") (pin "6") (pinfunction "RESET_6") (pintype "input"))
    )
    (net (code "80") (name "SCL") (class "Default")
      (node (ref "R9.15") (pin "1") (pinfunction "1_1") (pintype "passive"))
      (node (ref "SJ9") (pin "2") (pinfunction "2_2") (pintype "passive"))
      (node (ref "TP11") (pin "TP") (pinfunction "TP_TP") (pintype "input"))
      (node (ref "X9.01") (pin "3") (pinfunction "3_3") (pintype "passive"))
      (node (ref "X9.01") (pin "4") (pinfunction "4_4") (pintype "passive"))
    )
    (net (code "81") (name "SCLK") (class "Default")
      (node (ref "R9.04") (pin "2") (pinfunction "2_2") (pintype "passive"))
      (node (ref "SJ15") (pin "2") (pinfunction "2_2") (pintype "passive"))
      (node (ref "TP14") (pin "TP") (pinfunction "TP_TP") (pintype "input"))
    )
    (net (code "82") (name "SDA") (class "Default")
      (node (ref "R9.14") (pin "1") (pinfunction "1_1") (pintype "passive"))
      (node (ref "SJ10") (pin "2") (pinfunction "2_2") (pintype "passive"))
      (node (ref "TP10") (pin "TP") (pinfunction "TP_TP") (pintype "input"))
      (node (ref "X9.01") (pin "5") (pinfunction "5_5") (pintype "passive"))
      (node (ref "X9.01") (pin "6") (pinfunction "6_6") (pintype "passive"))
    )
    (net (code "83") (name "unconnected-(U9.00-NC-Pad11)") (class "Default")
      (node (ref "U9.00") (pin "11") (pinfunction "NC_11") (pintype "no_connect"))
    )
    (net (code "84") (name "unconnected-(U9.00-NC-Pad18)") (class "Default")
      (node (ref "U9.00") (pin "18") (pinfunction "NC_18") (pintype "no_connect"))
    )
    (net (code "85") (name "unconnected-(U9.00-NC-Pad20)") (class "Default")
      (node (ref "U9.00") (pin "20") (pinfunction "NC_20") (pintype "no_connect"))
    )
    (net (code "86") (name "unconnected-(U9.01-BYP-Pad4)") (class "Default")
      (node (ref "U9.01") (pin "4") (pinfunction "BYP_4") (pintype "input"))
    )
  )
)
